# Open_Reactor_Control_System_-_System_Int.net
KiCad netlist of a schematic drawn in Altium Designer
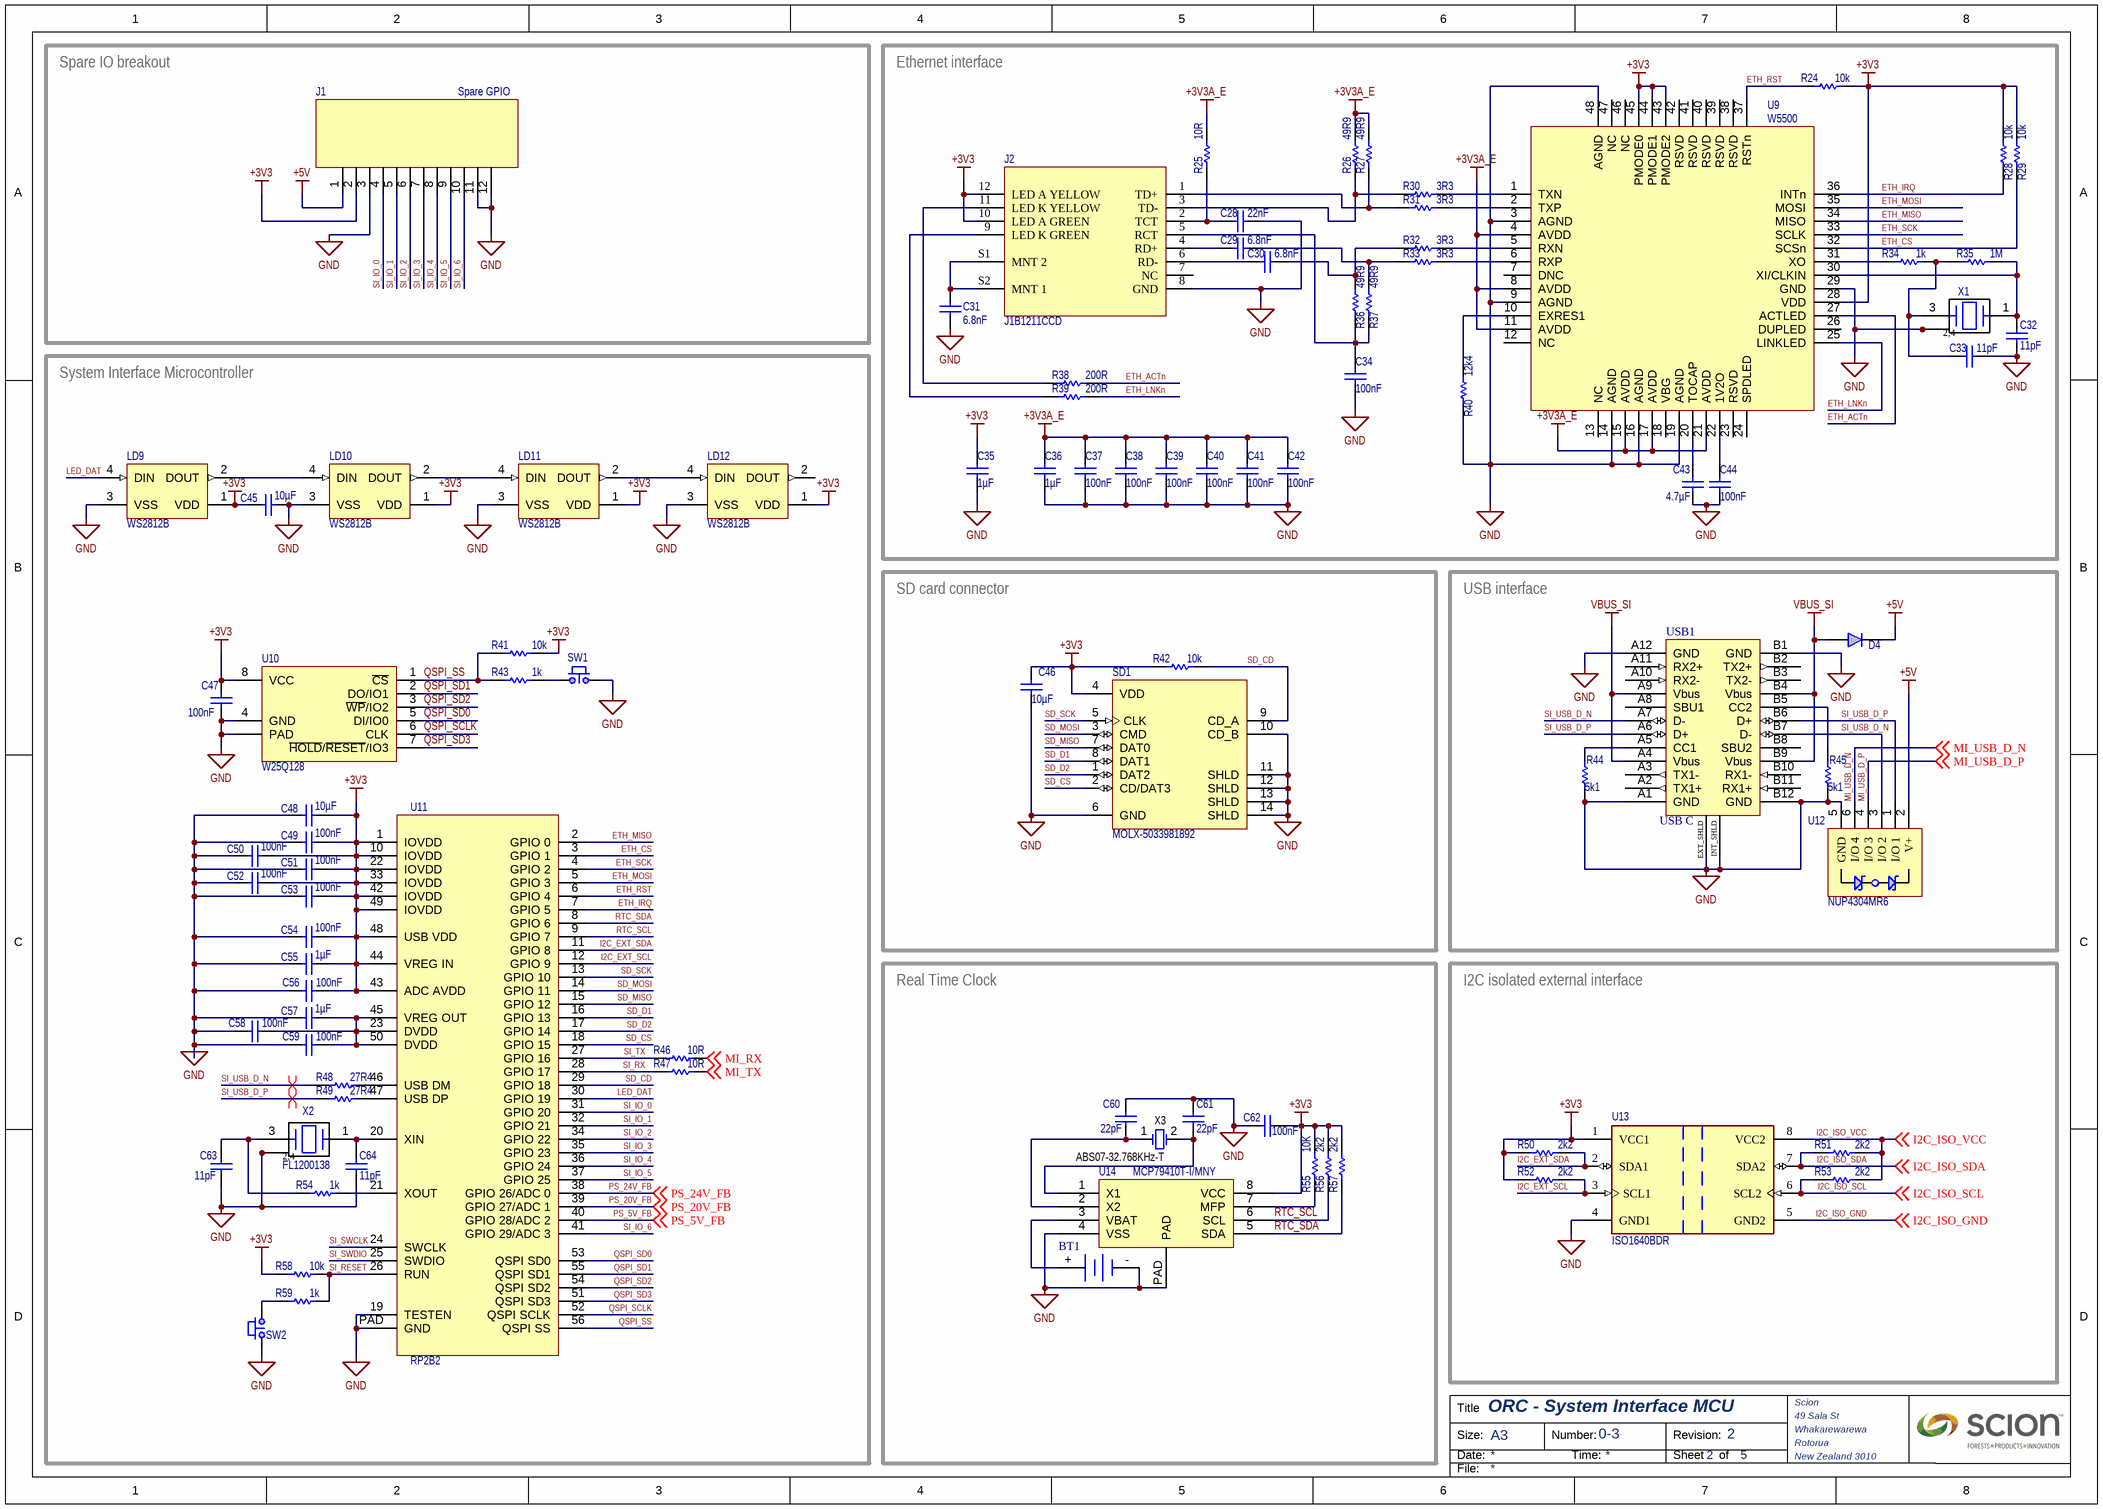
[diagram p0: Open Reactor Control System - System Interface MCU.SchDoc]

(export (version "E")
  (design (tool "Eeschema 10.0.6"))
  (components
    (comp (ref "BT1")
      (value "CR2032 Batt Holder")
      (footprint "CR2032 Batt Holder-Footprint-1")
      (description "SMD CR2032 coin cell holder")
      (libsource (lib "Scion Research") (part "CMP-00042-2"))
    )
    (comp (ref "C28")
      (value "22nF")
      (footprint "0603_CAP")
      (description "SMD Capacitor")
      (fields (field (name "Comment") "Capacitor"))
      (libsource (lib "Scion Research") (part "CMP-019-00005-2"))
    )
    (comp (ref "C29")
      (value "6.8nF")
      (footprint "0603_CAP")
      (description "SMD Capacitor")
      (fields (field (name "Comment") "Capacitor"))
      (libsource (lib "Scion Research") (part "CMP-019-00005-2"))
    )
    (comp (ref "C30")
      (value "6.8nF")
      (footprint "0603_CAP")
      (description "SMD Capacitor")
      (fields (field (name "Comment") "Capacitor"))
      (libsource (lib "Scion Research") (part "CMP-019-00005-2"))
    )
    (comp (ref "C31")
      (value "6.8nF")
      (footprint "0603_CAP")
      (description "SMD Capacitor")
      (fields (field (name "Comment") "Capacitor"))
      (libsource (lib "Scion Research") (part "CMP-019-00005-2"))
    )
    (comp (ref "C32")
      (value "11pF")
      (footprint "0603_CAP")
      (description "SMD Capacitor")
      (fields (field (name "Comment") "Capacitor"))
      (libsource (lib "Scion Research") (part "CMP-019-00005-2"))
    )
    (comp (ref "C33")
      (value "11pF")
      (footprint "0603_CAP")
      (description "SMD Capacitor")
      (fields (field (name "Comment") "Capacitor"))
      (libsource (lib "Scion Research") (part "CMP-019-00005-2"))
    )
    (comp (ref "C34")
      (value "100nF")
      (footprint "0603_CAP")
      (description "SMD Capacitor")
      (fields (field (name "Comment") "Capacitor"))
      (libsource (lib "Scion Research") (part "CMP-019-00005-2"))
    )
    (comp (ref "C35")
      (value "1µF")
      (footprint "0402_CAP")
      (description "SMD Capacitor")
      (fields (field (name "Comment") "Capacitor"))
      (libsource (lib "Scion Research") (part "CMP-019-00005-2"))
    )
    (comp (ref "C36")
      (value "1µF")
      (footprint "0402_CAP")
      (description "SMD Capacitor")
      (fields (field (name "Comment") "Capacitor"))
      (libsource (lib "Scion Research") (part "CMP-019-00005-2"))
    )
    (comp (ref "C37")
      (value "100nF")
      (footprint "0402_CAP")
      (description "SMD Capacitor")
      (fields (field (name "Comment") "Capacitor"))
      (libsource (lib "Scion Research") (part "CMP-019-00005-2"))
    )
    (comp (ref "C38")
      (value "100nF")
      (footprint "0402_CAP")
      (description "SMD Capacitor")
      (fields (field (name "Comment") "Capacitor"))
      (libsource (lib "Scion Research") (part "CMP-019-00005-2"))
    )
    (comp (ref "C39")
      (value "100nF")
      (footprint "0402_CAP")
      (description "SMD Capacitor")
      (fields (field (name "Comment") "Capacitor"))
      (libsource (lib "Scion Research") (part "CMP-019-00005-2"))
    )
    (comp (ref "C40")
      (value "100nF")
      (footprint "0402_CAP")
      (description "SMD Capacitor")
      (fields (field (name "Comment") "Capacitor"))
      (libsource (lib "Scion Research") (part "CMP-019-00005-2"))
    )
    (comp (ref "C41")
      (value "100nF")
      (footprint "0402_CAP")
      (description "SMD Capacitor")
      (fields (field (name "Comment") "Capacitor"))
      (libsource (lib "Scion Research") (part "CMP-019-00005-2"))
    )
    (comp (ref "C42")
      (value "100nF")
      (footprint "0402_CAP")
      (description "SMD Capacitor")
      (fields (field (name "Comment") "Capacitor"))
      (libsource (lib "Scion Research") (part "CMP-019-00005-2"))
    )
    (comp (ref "C43")
      (value "4.7µF")
      (footprint "0603_CAP")
      (description "SMD Capacitor")
      (fields (field (name "Comment") "Capacitor"))
      (libsource (lib "Scion Research") (part "CMP-019-00005-2"))
    )
    (comp (ref "C44")
      (value "100nF")
      (footprint "0402_CAP")
      (description "SMD Capacitor")
      (fields (field (name "Comment") "Capacitor"))
      (libsource (lib "Scion Research") (part "CMP-019-00005-2"))
    )
    (comp (ref "C45")
      (value "10µF")
      (footprint "0603_CAP")
      (description "SMD Capacitor")
      (fields (field (name "Comment") "Capacitor"))
      (libsource (lib "Scion Research") (part "CMP-019-00005-2"))
    )
    (comp (ref "C46")
      (value "10µF")
      (footprint "0603_CAP")
      (description "SMD Capacitor")
      (fields (field (name "Comment") "Capacitor"))
      (libsource (lib "Scion Research") (part "CMP-019-00005-2"))
    )
    (comp (ref "C47")
      (value "100nF")
      (footprint "0603_CAP")
      (description "SMD Capacitor")
      (fields (field (name "Comment") "Capacitor"))
      (libsource (lib "Scion Research") (part "CMP-019-00005-2"))
    )
    (comp (ref "C48")
      (value "10µF")
      (footprint "0603_CAP")
      (description "SMD Capacitor")
      (fields (field (name "Comment") "Capacitor"))
      (libsource (lib "Scion Research") (part "CMP-019-00005-2"))
    )
    (comp (ref "C49")
      (value "100nF")
      (footprint "0402_CAP")
      (description "SMD Capacitor")
      (fields (field (name "Comment") "Capacitor"))
      (libsource (lib "Scion Research") (part "CMP-019-00005-2"))
    )
    (comp (ref "C50")
      (value "100nF")
      (footprint "0402_CAP")
      (description "SMD Capacitor")
      (fields (field (name "Comment") "Capacitor"))
      (libsource (lib "Scion Research") (part "CMP-019-00005-2"))
    )
    (comp (ref "C51")
      (value "100nF")
      (footprint "0402_CAP")
      (description "SMD Capacitor")
      (fields (field (name "Comment") "Capacitor"))
      (libsource (lib "Scion Research") (part "CMP-019-00005-2"))
    )
    (comp (ref "C52")
      (value "100nF")
      (footprint "0402_CAP")
      (description "SMD Capacitor")
      (fields (field (name "Comment") "Capacitor"))
      (libsource (lib "Scion Research") (part "CMP-019-00005-2"))
    )
    (comp (ref "C53")
      (value "100nF")
      (footprint "0402_CAP")
      (description "SMD Capacitor")
      (fields (field (name "Comment") "Capacitor"))
      (libsource (lib "Scion Research") (part "CMP-019-00005-2"))
    )
    (comp (ref "C54")
      (value "100nF")
      (footprint "0402_CAP")
      (description "SMD Capacitor")
      (fields (field (name "Comment") "Capacitor"))
      (libsource (lib "Scion Research") (part "CMP-019-00005-2"))
    )
    (comp (ref "C55")
      (value "1µF")
      (footprint "0402_CAP")
      (description "SMD Capacitor")
      (fields (field (name "Comment") "Capacitor"))
      (libsource (lib "Scion Research") (part "CMP-019-00005-2"))
    )
    (comp (ref "C56")
      (value "100nF")
      (footprint "0402_CAP")
      (description "SMD Capacitor")
      (fields (field (name "Comment") "CMP-001-00172-2"))
      (libsource (lib "Scion Research") (part "CMP-019-00005-2"))
    )
    (comp (ref "C57")
      (value "1µF")
      (footprint "0402_CAP")
      (description "SMD Capacitor")
      (fields (field (name "Comment") "Capacitor"))
      (libsource (lib "Scion Research") (part "CMP-019-00005-2"))
    )
    (comp (ref "C58")
      (value "100nF")
      (footprint "0402_CAP")
      (description "SMD Capacitor")
      (fields (field (name "Comment") "CMP-001-00172-2"))
      (libsource (lib "Scion Research") (part "CMP-019-00005-2"))
    )
    (comp (ref "C59")
      (value "100nF")
      (footprint "0402_CAP")
      (description "SMD Capacitor")
      (fields (field (name "Comment") "CMP-001-00172-2"))
      (libsource (lib "Scion Research") (part "CMP-019-00005-2"))
    )
    (comp (ref "C60")
      (value "22pF")
      (footprint "0603_CAP")
      (description "SMD Capacitor")
      (fields (field (name "Comment") "Capacitor"))
      (libsource (lib "Scion Research") (part "CMP-019-00005-2"))
    )
    (comp (ref "C61")
      (value "22pF")
      (footprint "0603_CAP")
      (description "SMD Capacitor")
      (fields (field (name "Comment") "Capacitor"))
      (libsource (lib "Scion Research") (part "CMP-019-00005-2"))
    )
    (comp (ref "C62")
      (value "100nF")
      (footprint "0603_CAP")
      (description "SMD Capacitor")
      (fields (field (name "Comment") "Capacitor"))
      (libsource (lib "Scion Research") (part "CMP-019-00005-2"))
    )
    (comp (ref "C63")
      (value "11pF")
      (footprint "0603_CAP")
      (description "SMD Capacitor")
      (fields (field (name "Comment") "Capacitor"))
      (libsource (lib "Scion Research") (part "CMP-019-00005-2"))
    )
    (comp (ref "C64")
      (value "11pF")
      (footprint "0603_CAP")
      (description "SMD Capacitor")
      (fields (field (name "Comment") "Capacitor"))
      (libsource (lib "Scion Research") (part "CMP-019-00005-2"))
    )
    (comp (ref "D4")
      (value "Diode")
      (footprint "SOD-123")
      (description "SMD Diode")
      (libsource (lib "Scion Research") (part "Diode"))
    )
    (comp (ref "J1")
      (value "Spare GPIO")
      (footprint "12P DIP 2.54mm male header")
      (description "12 Pin Connector")
      (libsource (lib "Scion Research") (part "12_Pin"))
    )
    (comp (ref "J2")
      (value "J1B1211CCD")
      (footprint "FP-J1B1211CCD-MFG")
      (description "Telecom and Datacom Connector, 8 Contact(s), Female, Right Angle, Solder Terminal, Locking")
      (libsource (lib "Scion Research") (part "043a9053fb366fe6dc2bf5dbfb72c80"))
    )
    (comp (ref "LD9")
      (value "WS2812B")
      (footprint "WS2812B-2020")
      (fields (field (name "MANUFACTURER") "Adafruit Industries"))
      (libsource (lib "Scion Research") (part "CMP-007-00035-3"))
    )
    (comp (ref "LD10")
      (value "WS2812B")
      (footprint "WS2812B-2020")
      (fields (field (name "MANUFACTURER") "Adafruit Industries"))
      (libsource (lib "Scion Research") (part "CMP-007-00035-3"))
    )
    (comp (ref "LD11")
      (value "WS2812B")
      (footprint "WS2812B-2020")
      (fields (field (name "MANUFACTURER") "Adafruit Industries"))
      (libsource (lib "Scion Research") (part "CMP-007-00035-3"))
    )
    (comp (ref "LD12")
      (value "WS2812B")
      (footprint "WS2812B-2020")
      (fields (field (name "MANUFACTURER") "Adafruit Industries"))
      (libsource (lib "Scion Research") (part "CMP-007-00035-3"))
    )
    (comp (ref "R24")
      (value "Resistor")
      (footprint "0603_RES")
      (description "SMD Resistor")
      (fields (field (name "ALTIUM_VALUE") "10k"))
      (libsource (lib "Scion Research") (part "CMP-009-00177-2"))
    )
    (comp (ref "R25")
      (value "Resistor")
      (footprint "0603_RES")
      (description "SMD Resistor")
      (fields (field (name "ALTIUM_VALUE") "10R"))
      (libsource (lib "Scion Research") (part "CMP-009-00177-2"))
    )
    (comp (ref "R26")
      (value "Resistor")
      (footprint "0603_RES")
      (description "SMD Resistor")
      (fields (field (name "ALTIUM_VALUE") "49R9"))
      (libsource (lib "Scion Research") (part "CMP-009-00177-2"))
    )
    (comp (ref "R27")
      (value "Resistor")
      (footprint "0603_RES")
      (description "SMD Resistor")
      (fields (field (name "ALTIUM_VALUE") "49R9"))
      (libsource (lib "Scion Research") (part "CMP-009-00177-2"))
    )
    (comp (ref "R28")
      (value "10k")
      (footprint "0603_RES")
      (description "SMD Resistor")
      (fields (field (name "Comment") "Resistor"))
      (libsource (lib "Scion Research") (part "CMP-009-00177-2"))
    )
    (comp (ref "R29")
      (value "10k")
      (footprint "0603_RES")
      (description "SMD Resistor")
      (fields (field (name "Comment") "Resistor"))
      (libsource (lib "Scion Research") (part "CMP-009-00177-2"))
    )
    (comp (ref "R30")
      (value "Resistor")
      (footprint "0603_RES")
      (description "SMD Resistor")
      (fields (field (name "ALTIUM_VALUE") "3R3"))
      (libsource (lib "Scion Research") (part "CMP-009-00177-2"))
    )
    (comp (ref "R31")
      (value "Resistor")
      (footprint "0603_RES")
      (description "SMD Resistor")
      (fields (field (name "ALTIUM_VALUE") "3R3"))
      (libsource (lib "Scion Research") (part "CMP-009-00177-2"))
    )
    (comp (ref "R32")
      (value "Resistor")
      (footprint "0603_RES")
      (description "SMD Resistor")
      (fields (field (name "ALTIUM_VALUE") "3R3"))
      (libsource (lib "Scion Research") (part "CMP-009-00177-2"))
    )
    (comp (ref "R33")
      (value "Resistor")
      (footprint "0603_RES")
      (description "SMD Resistor")
      (fields (field (name "ALTIUM_VALUE") "3R3"))
      (libsource (lib "Scion Research") (part "CMP-009-00177-2"))
    )
    (comp (ref "R34")
      (value "Resistor")
      (footprint "0603_RES")
      (description "SMD Resistor")
      (fields (field (name "ALTIUM_VALUE") "1k"))
      (libsource (lib "Scion Research") (part "CMP-009-00177-2"))
    )
    (comp (ref "R35")
      (value "Resistor")
      (footprint "0603_RES")
      (description "SMD Resistor")
      (fields (field (name "ALTIUM_VALUE") "1M"))
      (libsource (lib "Scion Research") (part "CMP-009-00177-2"))
    )
    (comp (ref "R36")
      (value "Resistor")
      (footprint "0603_RES")
      (description "SMD Resistor")
      (fields (field (name "ALTIUM_VALUE") "49R9"))
      (libsource (lib "Scion Research") (part "CMP-009-00177-2"))
    )
    (comp (ref "R37")
      (value "Resistor")
      (footprint "0603_RES")
      (description "SMD Resistor")
      (fields (field (name "ALTIUM_VALUE") "49R9"))
      (libsource (lib "Scion Research") (part "CMP-009-00177-2"))
    )
    (comp (ref "R38")
      (value "Resistor")
      (footprint "0603_RES")
      (description "SMD Resistor")
      (fields (field (name "ALTIUM_VALUE") "200R"))
      (libsource (lib "Scion Research") (part "CMP-009-00177-2"))
    )
    (comp (ref "R39")
      (value "Resistor")
      (footprint "0603_RES")
      (description "SMD Resistor")
      (fields (field (name "ALTIUM_VALUE") "200R"))
      (libsource (lib "Scion Research") (part "CMP-009-00177-2"))
    )
    (comp (ref "R40")
      (value "12k4")
      (footprint "0603_RES")
      (description "SMD Resistor")
      (fields (field (name "Comment") "Resistor"))
      (libsource (lib "Scion Research") (part "CMP-009-00177-2"))
    )
    (comp (ref "R41")
      (value "10k")
      (footprint "0603_RES")
      (description "SMD Resistor")
      (fields (field (name "Comment") "Resistor"))
      (libsource (lib "Scion Research") (part "CMP-009-00177-2"))
    )
    (comp (ref "R42")
      (value "Resistor")
      (footprint "0603_RES")
      (description "SMD Resistor")
      (fields (field (name "ALTIUM_VALUE") "10k"))
      (libsource (lib "Scion Research") (part "CMP-009-00177-2"))
    )
    (comp (ref "R43")
      (value "1k")
      (footprint "0603_RES")
      (description "SMD Resistor")
      (fields (field (name "Comment") "Resistor"))
      (libsource (lib "Scion Research") (part "CMP-009-00177-2"))
    )
    (comp (ref "R44")
      (value "Resistor")
      (footprint "0603_RES")
      (description "SMD Resistor")
      (fields (field (name "ALTIUM_VALUE") "5k1"))
      (libsource (lib "Scion Research") (part "CMP-009-00177-2"))
    )
    (comp (ref "R45")
      (value "Resistor")
      (footprint "0603_RES")
      (description "SMD Resistor")
      (fields (field (name "ALTIUM_VALUE") "5k1"))
      (libsource (lib "Scion Research") (part "CMP-009-00177-2"))
    )
    (comp (ref "R46")
      (value "10R")
      (footprint "0603_RES")
      (description "SMD Resistor")
      (fields (field (name "Comment") "Resistor"))
      (libsource (lib "Scion Research") (part "CMP-009-00177-2"))
    )
    (comp (ref "R47")
      (value "10R")
      (footprint "0603_RES")
      (description "SMD Resistor")
      (fields (field (name "Comment") "Resistor"))
      (libsource (lib "Scion Research") (part "CMP-009-00177-2"))
    )
    (comp (ref "R48")
      (value "Resistor")
      (footprint "0603_RES")
      (description "SMD Resistor")
      (fields (field (name "ALTIUM_VALUE") "27R4"))
      (libsource (lib "Scion Research") (part "CMP-009-00177-2"))
    )
    (comp (ref "R49")
      (value "Resistor")
      (footprint "0603_RES")
      (description "SMD Resistor")
      (fields (field (name "ALTIUM_VALUE") "27R4"))
      (libsource (lib "Scion Research") (part "CMP-009-00177-2"))
    )
    (comp (ref "R50")
      (value "2k2")
      (footprint "0603_RES")
      (description "SMD Resistor")
      (fields (field (name "Comment") "Resistor"))
      (libsource (lib "Scion Research") (part "CMP-009-00177-2"))
    )
    (comp (ref "R51")
      (value "2k2")
      (footprint "0603_RES")
      (description "SMD Resistor")
      (fields (field (name "Comment") "Resistor"))
      (libsource (lib "Scion Research") (part "CMP-009-00177-2"))
    )
    (comp (ref "R52")
      (value "2k2")
      (footprint "0603_RES")
      (description "SMD Resistor")
      (fields (field (name "Comment") "Resistor"))
      (libsource (lib "Scion Research") (part "CMP-009-00177-2"))
    )
    (comp (ref "R53")
      (value "2k2")
      (footprint "0603_RES")
      (description "SMD Resistor")
      (fields (field (name "Comment") "Resistor"))
      (libsource (lib "Scion Research") (part "CMP-009-00177-2"))
    )
    (comp (ref "R54")
      (value "Resistor")
      (footprint "0603_RES")
      (description "SMD Resistor")
      (fields (field (name "ALTIUM_VALUE") "1k"))
      (libsource (lib "Scion Research") (part "CMP-009-00177-2"))
    )
    (comp (ref "R55")
      (value "10K")
      (footprint "0603_RES")
      (description "SMD Resistor")
      (fields (field (name "Comment") "Resistor"))
      (libsource (lib "Scion Research") (part "CMP-009-00177-2"))
    )
    (comp (ref "R56")
      (value "2k2")
      (footprint "0603_RES")
      (description "SMD Resistor")
      (fields (field (name "Comment") "Resistor"))
      (libsource (lib "Scion Research") (part "CMP-009-00177-2"))
    )
    (comp (ref "R57")
      (value "2k2")
      (footprint "0603_RES")
      (description "SMD Resistor")
      (fields (field (name "Comment") "Resistor"))
      (libsource (lib "Scion Research") (part "CMP-009-00177-2"))
    )
    (comp (ref "R58")
      (value "10k")
      (footprint "0603_RES")
      (description "SMD Resistor")
      (fields (field (name "Comment") "Resistor"))
      (libsource (lib "Scion Research") (part "CMP-009-00177-2"))
    )
    (comp (ref "R59")
      (value "1k")
      (footprint "0603_RES")
      (description "SMD Resistor")
      (fields (field (name "Comment") "Resistor"))
      (libsource (lib "Scion Research") (part "CMP-009-00177-2"))
    )
    (comp (ref "SD1")
      (value "MOLX-5033981892")
      (footprint "MOLX-5033981892_V")
      (libsource (lib "Scion Research") (part "CMP-002-00049-5"))
    )
    (comp (ref "SW1")
      (value "EVP-AAN02Q")
      (footprint "FP-EVP-AAN02Q-MFG")
      (description "Switch Tactile N.O. SPST Rectangular Button J-Bend 0.02A 15VDC 100000Cycles 5N SMD T/R")
      (libsource (lib "Scion Research") (part "67890d47754ac483cb1d3ba3be74b6c"))
    )
    (comp (ref "SW2")
      (value "EVP-AAN02Q")
      (footprint "FP-EVP-AAN02Q-MFG")
      (description "Switch Tactile N.O. SPST Rectangular Button J-Bend 0.02A 15VDC 100000Cycles 5N SMD T/R")
      (libsource (lib "Scion Research") (part "67890d47754ac483cb1d3ba3be74b6c"))
    )
    (comp (ref "U9")
      (value "W5500")
      (footprint "TSQFP50P900X900X160-48N")
      (description "Microprocessor Circuit, CMOS, PQFP48")
      (libsource (lib "Scion Research") (part "W5500-Symbol-1"))
    )
    (comp (ref "U10")
      (value "W25Q128")
      (footprint "SOIC127P790X216-8N")
      (description "W25Q16-256 SPI flash module")
      (libsource (lib "Scion Research") (part "W25Qxx-Symbol"))
    )
    (comp (ref "U11")
      (value "RP2B2")
      (footprint "QFN40P700X700X90_HS-57N")
      (description "RP2040 Arm Cortex M0+ Dual Core MCU")
      (libsource (lib "Scion Research") (part "RP2B2-Symbol-1"))
    )
    (comp (ref "U12")
      (value "NUP4304MR6")
      (footprint "TSOP-6")
      (description "ESD Protection Doide Array")
      (libsource (lib "Scion Research") (part "CMP-004-0028-1"))
    )
    (comp (ref "U13")
      (value "ISO1640BDR")
      (footprint "FP-D0008A-IPC_B")
      (description "Interface Circuit, PDSO8")
      (libsource (lib "Scion Research") (part "4cc1386e94c7f9b5035976a599e6ca5"))
    )
    (comp (ref "U14")
      (value "MCP79410T-I/MNY")
      (footprint "MCP79410T-I_MNY-Footprint-1")
      (description "Real Time Clock Serial 64byte Clock/Calendar/Alarm/Battery Backup Automotive 8-Pin TDFN EP T/R")
      (libsource (lib "Scion Research") (part "CMP-00046-1"))
    )
    (comp (ref "USB1")
      (value "USB C")
      (footprint "GT-USB-7010ASV")
      (description "Vertical or RA Type C Usb Connector Rohs Compliant: Yes")
      (libsource (lib "Scion Research") (part "CMP-00005-5"))
    )
    (comp (ref "X1")
      (value "ABM8-25.000MHZ-12-D1X-T")
      (footprint "3225 CRYSTAL 12MHz")
      (description "SMD Crystal")
      (libsource (lib "Scion Research") (part "Crystal 4-pin 3225"))
    )
    (comp (ref "X2")
      (value "FL1200138")
      (footprint "3225 CRYSTAL 12MHz")
      (description "SMD Crystal")
      (libsource (lib "Scion Research") (part "Crystal 4-pin 3225"))
    )
    (comp (ref "X3")
      (value "ABS07-32.768KHz-T")
      (footprint "ABRA-ABS07-2_V")
      (fields (field (name "TOLERANCE") "20ppm") (field (name "MANUFACTURER") "Abracon"))
      (libsource (lib "Scion Research") (part "CMP-003-00022-1"))
    )
  )
  (nets
    (net (code "1") (name "+3V3") (class "Default")
      (node (ref "C35") (pin "2") (pinfunction "2_2") (pintype "passive"))
      (node (ref "C45") (pin "2") (pinfunction "2_2") (pintype "passive"))
      (node (ref "C46") (pin "1") (pinfunction "1_1") (pintype "passive"))
      (node (ref "C47") (pin "1") (pinfunction "1_1") (pintype "passive"))
      (node (ref "C48") (pin "1") (pinfunction "1_1") (pintype "passive"))
      (node (ref "C49") (pin "1") (pinfunction "1_1") (pintype "passive"))
      (node (ref "C50") (pin "1") (pinfunction "1_1") (pintype "passive"))
      (node (ref "C51") (pin "1") (pinfunction "1_1") (pintype "passive"))
      (node (ref "C52") (pin "1") (pinfunction "1_1") (pintype "passive"))
      (node (ref "C53") (pin "1") (pinfunction "1_1") (pintype "passive"))
      (node (ref "C54") (pin "1") (pinfunction "1_1") (pintype "passive"))
      (node (ref "C55") (pin "1") (pinfunction "1_1") (pintype "passive"))
      (node (ref "C56") (pin "2") (pinfunction "2_2") (pintype "passive"))
      (node (ref "C62") (pin "1") (pinfunction "1_1") (pintype "passive"))
      (node (ref "J1") (pin "2") (pinfunction "2_2") (pintype "passive"))
      (node (ref "J2") (pin "10") (pinfunction "LED_A_GREEN_10") (pintype "passive"))
      (node (ref "J2") (pin "12") (pinfunction "LED_A_YELLOW_12") (pintype "passive"))
      (node (ref "LD10") (pin "1") (pinfunction "VDD_1") (pintype "power_in"))
      (node (ref "LD11") (pin "1") (pinfunction "VDD_1") (pintype "power_in"))
      (node (ref "LD12") (pin "1") (pinfunction "VDD_1") (pintype "power_in"))
      (node (ref "LD9") (pin "1") (pinfunction "VDD_1") (pintype "power_in"))
      (node (ref "R24") (pin "2") (pinfunction "2_2") (pintype "passive"))
      (node (ref "R28") (pin "2") (pinfunction "2_2") (pintype "passive"))
      (node (ref "R29") (pin "2") (pinfunction "2_2") (pintype "passive"))
      (node (ref "R41") (pin "2") (pinfunction "2_2") (pintype "passive"))
      (node (ref "R42") (pin "2") (pinfunction "2_2") (pintype "passive"))
      (node (ref "R50") (pin "2") (pinfunction "2_2") (pintype "passive"))
      (node (ref "R52") (pin "2") (pinfunction "2_2") (pintype "passive"))
      (node (ref "R55") (pin "2") (pinfunction "2_2") (pintype "passive"))
      (node (ref "R56") (pin "1") (pinfunction "1_1") (pintype "passive"))
      (node (ref "R57") (pin "1") (pinfunction "1_1") (pintype "passive"))
      (node (ref "R58") (pin "2") (pinfunction "2_2") (pintype "passive"))
      (node (ref "SD1") (pin "4") (pinfunction "VDD_4") (pintype "power_in"))
      (node (ref "U10") (pin "8") (pinfunction "VCC_8") (pintype "passive"))
      (node (ref "U11") (pin "1") (pinfunction "IOVDD_1") (pintype "passive"))
      (node (ref "U11") (pin "10") (pinfunction "IOVDD_10") (pintype "passive"))
      (node (ref "U11") (pin "22") (pinfunction "IOVDD_22") (pintype "passive"))
      (node (ref "U11") (pin "33") (pinfunction "IOVDD_33") (pintype "passive"))
      (node (ref "U11") (pin "42") (pinfunction "IOVDD_42") (pintype "passive"))
      (node (ref "U11") (pin "43") (pinfunction "ADC_AVDD_43") (pintype "passive"))
      (node (ref "U11") (pin "44") (pinfunction "VREG_IN_44") (pintype "passive"))
      (node (ref "U11") (pin "48") (pinfunction "USB_VDD_48") (pintype "passive"))
      (node (ref "U11") (pin "49") (pinfunction "IOVDD_49") (pintype "passive"))
      (node (ref "U13") (pin "1") (pinfunction "VCC1_1") (pintype "power_in"))
      (node (ref "U14") (pin "8") (pinfunction "VCC_8") (pintype "passive"))
      (node (ref "U9") (pin "28") (pinfunction "VDD_28") (pintype "passive"))
      (node (ref "U9") (pin "43") (pinfunction "PMODE2_43") (pintype "passive"))
      (node (ref "U9") (pin "44") (pinfunction "PMODE1_44") (pintype "passive"))
      (node (ref "U9") (pin "45") (pinfunction "PMODE0_45") (pintype "passive"))
    )
    (net (code "2") (name "+3V3A_E") (class "Default")
      (node (ref "C36") (pin "2") (pinfunction "2_2") (pintype "passive"))
      (node (ref "C37") (pin "2") (pinfunction "2_2") (pintype "passive"))
      (node (ref "C38") (pin "2") (pinfunction "2_2") (pintype "passive"))
      (node (ref "C39") (pin "2") (pinfunction "2_2") (pintype "passive"))
      (node (ref "C40") (pin "2") (pinfunction "2_2") (pintype "passive"))
      (node (ref "C41") (pin "2") (pinfunction "2_2") (pintype "passive"))
      (node (ref "C42") (pin "2") (pinfunction "2_2") (pintype "passive"))
      (node (ref "R25") (pin "2") (pinfunction "2_2") (pintype "passive"))
      (node (ref "R26") (pin "2") (pinfunction "2_2") (pintype "passive"))
      (node (ref "R27") (pin "2") (pinfunction "2_2") (pintype "passive"))
      (node (ref "U9") (pin "11") (pinfunction "AVDD_11") (pintype "passive"))
      (node (ref "U9") (pin "15") (pinfunction "AVDD_15") (pintype "passive"))
      (node (ref "U9") (pin "17") (pinfunction "AVDD_17") (pintype "passive"))
      (node (ref "U9") (pin "21") (pinfunction "AVDD_21") (pintype "passive"))
      (node (ref "U9") (pin "4") (pinfunction "AVDD_4") (pintype "passive"))
      (node (ref "U9") (pin "8") (pinfunction "AVDD_8") (pintype "passive"))
    )
    (net (code "3") (name "+5V") (class "Default")
      (node (ref "D4") (pin "1") (pinfunction "K_1") (pintype "passive"))
      (node (ref "J1") (pin "1") (pinfunction "1_1") (pintype "passive"))
      (node (ref "U12") (pin "2") (pinfunction "V+_2") (pintype "power_in"))
    )
    (net (code "4") (name "/ETH_ACTn") (class "Default")
      (node (ref "R38") (pin "2") (pinfunction "2_2") (pintype "passive"))
      (node (ref "U9") (pin "27") (pinfunction "ACTLED_27") (pintype "passive"))
    )
    (net (code "5") (name "/ETH_CS") (class "Default")
      (node (ref "R29") (pin "1") (pinfunction "1_1") (pintype "passive"))
      (node (ref "U11") (pin "3") (pinfunction "GPIO_1_3") (pintype "passive"))
      (node (ref "U9") (pin "32") (pinfunction "SCSn_32") (pintype "passive"))
    )
    (net (code "6") (name "/ETH_IRQ") (class "Default")
      (node (ref "R28") (pin "1") (pinfunction "1_1") (pintype "passive"))
      (node (ref "U11") (pin "7") (pinfunction "GPIO_5_7") (pintype "passive"))
      (node (ref "U9") (pin "36") (pinfunction "INTn_36") (pintype "passive"))
    )
    (net (code "7") (name "/ETH_LNKn") (class "Default")
      (node (ref "R39") (pin "2") (pinfunction "2_2") (pintype "passive"))
      (node (ref "U9") (pin "25") (pinfunction "LINKLED_25") (pintype "passive"))
    )
    (net (code "8") (name "/ETH_MISO") (class "Default")
      (node (ref "U11") (pin "2") (pinfunction "GPIO_0_2") (pintype "passive"))
      (node (ref "U9") (pin "34") (pinfunction "MISO_34") (pintype "passive"))
    )
    (net (code "9") (name "/ETH_MOSI") (class "Default")
      (node (ref "U11") (pin "5") (pinfunction "GPIO_3_5") (pintype "passive"))
      (node (ref "U9") (pin "35") (pinfunction "MOSI_35") (pintype "passive"))
    )
    (net (code "10") (name "/ETH_RST") (class "Default")
      (node (ref "R24") (pin "1") (pinfunction "1_1") (pintype "passive"))
      (node (ref "U11") (pin "6") (pinfunction "GPIO_4_6") (pintype "passive"))
      (node (ref "U9") (pin "37") (pinfunction "RSTn_37") (pintype "passive"))
    )
    (net (code "11") (name "/ETH_SCK") (class "Default")
      (node (ref "U11") (pin "4") (pinfunction "GPIO_2_4") (pintype "passive"))
      (node (ref "U9") (pin "33") (pinfunction "SCLK_33") (pintype "passive"))
    )
    (net (code "12") (name "/I2C_EXT_SCL") (class "Default")
      (node (ref "R52") (pin "1") (pinfunction "1_1") (pintype "passive"))
      (node (ref "U11") (pin "12") (pinfunction "GPIO_9_12") (pintype "passive"))
      (node (ref "U13") (pin "3") (pinfunction "SCL1_3") (pintype "input"))
    )
    (net (code "13") (name "/I2C_EXT_SDA") (class "Default")
      (node (ref "R50") (pin "1") (pinfunction "1_1") (pintype "passive"))
      (node (ref "U11") (pin "11") (pinfunction "GPIO_8_11") (pintype "passive"))
      (node (ref "U13") (pin "2") (pinfunction "SDA1_2") (pintype "bidirectional"))
    )
    (net (code "14") (name "/LED_DAT") (class "Default")
      (node (ref "LD9") (pin "4") (pinfunction "DIN_4") (pintype "input"))
      (node (ref "U11") (pin "30") (pinfunction "GPIO_19_30") (pintype "passive"))
    )
    (net (code "15") (name "/QSPI_SCLK") (class "Default")
      (node (ref "U10") (pin "6") (pinfunction "CLK_6") (pintype "passive"))
      (node (ref "U11") (pin "52") (pinfunction "QSPI_SCLK_52") (pintype "passive"))
    )
    (net (code "16") (name "/QSPI_SD0") (class "Default")
      (node (ref "U10") (pin "5") (pinfunction "DI/IO0_5") (pintype "passive"))
      (node (ref "U11") (pin "53") (pinfunction "QSPI_SD0_53") (pintype "passive"))
    )
    (net (code "17") (name "/QSPI_SD1") (class "Default")
      (node (ref "U10") (pin "2") (pinfunction "DO/IO1_2") (pintype "passive"))
      (node (ref "U11") (pin "55") (pinfunction "QSPI_SD1_55") (pintype "passive"))
    )
    (net (code "18") (name "/QSPI_SD2") (class "Default")
      (node (ref "U10") (pin "3") (pinfunction "~{WP}/IO2_3") (pintype "passive"))
      (node (ref "U11") (pin "54") (pinfunction "QSPI_SD2_54") (pintype "passive"))
    )
    (net (code "19") (name "/QSPI_SD3") (class "Default")
      (node (ref "U10") (pin "7") (pinfunction "~{HOLD}/~{RESET}/IO3_7") (pintype "passive"))
      (node (ref "U11") (pin "51") (pinfunction "QSPI_SD3_51") (pintype "passive"))
    )
    (net (code "20") (name "/QSPI_SS") (class "Default")
      (node (ref "R41") (pin "1") (pinfunction "1_1") (pintype "passive"))
      (node (ref "R43") (pin "2") (pinfunction "2_2") (pintype "passive"))
      (node (ref "U10") (pin "1") (pinfunction "~{CS}_1") (pintype "passive"))
      (node (ref "U11") (pin "56") (pinfunction "QSPI_SS_56") (pintype "passive"))
    )
    (net (code "21") (name "/RTC_SCL") (class "Default")
      (node (ref "R56") (pin "2") (pinfunction "2_2") (pintype "passive"))
      (node (ref "U11") (pin "9") (pinfunction "GPIO_7_9") (pintype "passive"))
      (node (ref "U14") (pin "6") (pinfunction "SCL_6") (pintype "passive"))
    )
    (net (code "22") (name "/RTC_SDA") (class "Default")
      (node (ref "R57") (pin "2") (pinfunction "2_2") (pintype "passive"))
      (node (ref "U11") (pin "8") (pinfunction "GPIO_6_8") (pintype "passive"))
      (node (ref "U14") (pin "5") (pinfunction "SDA_5") (pintype "passive"))
    )
    (net (code "23") (name "/SD_CD") (class "Default")
      (node (ref "R42") (pin "1") (pinfunction "1_1") (pintype "passive"))
      (node (ref "SD1") (pin "9") (pinfunction "CD_A_9") (pintype "passive"))
      (node (ref "U11") (pin "29") (pinfunction "GPIO_18_29") (pintype "passive"))
    )
    (net (code "24") (name "/SD_CS") (class "Default")
      (node (ref "SD1") (pin "2") (pinfunction "CD/DAT3_2") (pintype "bidirectional"))
      (node (ref "U11") (pin "18") (pinfunction "GPIO_15_18") (pintype "passive"))
    )
    (net (code "25") (name "/SD_D1") (class "Default")
      (node (ref "SD1") (pin "8") (pinfunction "DAT1_8") (pintype "bidirectional"))
      (node (ref "U11") (pin "16") (pinfunction "GPIO_13_16") (pintype "passive"))
    )
    (net (code "26") (name "/SD_D2") (class "Default")
      (node (ref "SD1") (pin "1") (pinfunction "DAT2_1") (pintype "bidirectional"))
      (node (ref "U11") (pin "17") (pinfunction "GPIO_14_17") (pintype "passive"))
    )
    (net (code "27") (name "/SD_MISO") (class "Default")
      (node (ref "SD1") (pin "7") (pinfunction "DAT0_7") (pintype "bidirectional"))
      (node (ref "U11") (pin "15") (pinfunction "GPIO_12_15") (pintype "passive"))
    )
    (net (code "28") (name "/SD_MOSI") (class "Default")
      (node (ref "SD1") (pin "3") (pinfunction "CMD_3") (pintype "bidirectional"))
      (node (ref "U11") (pin "14") (pinfunction "GPIO_11_14") (pintype "passive"))
    )
    (net (code "29") (name "/SD_SCK") (class "Default")
      (node (ref "SD1") (pin "5") (pinfunction "CLK_5") (pintype "input"))
      (node (ref "U11") (pin "13") (pinfunction "GPIO_10_13") (pintype "passive"))
    )
    (net (code "30") (name "/SI_IO_0") (class "Default")
      (node (ref "J1") (pin "4") (pinfunction "4_4") (pintype "passive"))
      (node (ref "U11") (pin "31") (pinfunction "GPIO_20_31") (pintype "passive"))
    )
    (net (code "31") (name "/SI_IO_1") (class "Default")
      (node (ref "J1") (pin "5") (pinfunction "5_5") (pintype "passive"))
      (node (ref "U11") (pin "32") (pinfunction "GPIO_21_32") (pintype "passive"))
    )
    (net (code "32") (name "/SI_IO_2") (class "Default")
      (node (ref "J1") (pin "6") (pinfunction "6_6") (pintype "passive"))
      (node (ref "U11") (pin "34") (pinfunction "GPIO_22_34") (pintype "passive"))
    )
    (net (code "33") (name "/SI_IO_3") (class "Default")
      (node (ref "J1") (pin "7") (pinfunction "7_7") (pintype "passive"))
      (node (ref "U11") (pin "35") (pinfunction "GPIO_23_35") (pintype "passive"))
    )
    (net (code "34") (name "/SI_IO_4") (class "Default")
      (node (ref "J1") (pin "8") (pinfunction "8_8") (pintype "passive"))
      (node (ref "U11") (pin "36") (pinfunction "GPIO_24_36") (pintype "passive"))
    )
    (net (code "35") (name "/SI_IO_5") (class "Default")
      (node (ref "J1") (pin "9") (pinfunction "9_9") (pintype "passive"))
      (node (ref "U11") (pin "37") (pinfunction "GPIO_25_37") (pintype "passive"))
    )
    (net (code "36") (name "/SI_IO_6") (class "Default")
      (node (ref "J1") (pin "10") (pinfunction "10_10") (pintype "passive"))
      (node (ref "U11") (pin "41") (pinfunction "GPIO_29/ADC_3_41") (pintype "passive"))
    )
    (net (code "37") (name "/SI_RESET") (class "Default")
      (node (ref "R58") (pin "1") (pinfunction "1_1") (pintype "passive"))
      (node (ref "R59") (pin "1") (pinfunction "1_1") (pintype "passive"))
      (node (ref "U11") (pin "26") (pinfunction "RUN_26") (pintype "passive"))
    )
    (net (code "38") (name "/SI_RX") (class "Default")
      (node (ref "R47") (pin "2") (pinfunction "2_2") (pintype "passive"))
      (node (ref "U11") (pin "28") (pinfunction "GPIO_17_28") (pintype "passive"))
    )
    (net (code "39") (name "/SI_SWCLK") (class "Default")
      (node (ref "U11") (pin "24") (pinfunction "SWCLK_24") (pintype "passive"))
    )
    (net (code "40") (name "/SI_SWDIO") (class "Default")
      (node (ref "U11") (pin "25") (pinfunction "SWDIO_25") (pintype "passive"))
    )
    (net (code "41") (name "/SI_TX") (class "Default")
      (node (ref "R46") (pin "2") (pinfunction "2_2") (pintype "passive"))
      (node (ref "U11") (pin "27") (pinfunction "GPIO_16_27") (pintype "passive"))
    )
    (net (code "42") (name "/SI_USB_D_N") (class "Default")
      (node (ref "R48") (pin "1") (pinfunction "1_1") (pintype "passive"))
      (node (ref "U12") (pin "3") (pinfunction "I/O_2_3") (pintype "power_in"))
      (node (ref "USB1") (pin "A7") (pinfunction "D-_A7") (pintype "bidirectional"))
      (node (ref "USB1") (pin "B7") (pinfunction "D-_B7") (pintype "bidirectional"))
    )
    (net (code "43") (name "/SI_USB_D_P") (class "Default")
      (node (ref "R49") (pin "1") (pinfunction "1_1") (pintype "passive"))
      (node (ref "U12") (pin "1") (pinfunction "I/O_1_1") (pintype "power_in"))
      (node (ref "USB1") (pin "A6") (pinfunction "D+_A6") (pintype "bidirectional"))
      (node (ref "USB1") (pin "B6") (pinfunction "D+_B6") (pintype "bidirectional"))
    )
    (net (code "44") (name "GND") (class "Default")
      (node (ref "BT1") (pin "-") (pinfunction "-_-") (pintype "passive"))
      (node (ref "C28") (pin "1") (pinfunction "1_1") (pintype "passive"))
      (node (ref "C31") (pin "2") (pinfunction "2_2") (pintype "passive"))
      (node (ref "C32") (pin "2") (pinfunction "2_2") (pintype "passive"))
      (node (ref "C33") (pin "2") (pinfunction "2_2") (pintype "passive"))
      (node (ref "C34") (pin "1") (pinfunction "1_1") (pintype "passive"))
      (node (ref "C35") (pin "1") (pinfunction "1_1") (pintype "passive"))
      (node (ref "C36") (pin "1") (pinfunction "1_1") (pintype "passive"))
      (node (ref "C37") (pin "1") (pinfunction "1_1") (pintype "passive"))
      (node (ref "C38") (pin "1") (pinfunction "1_1") (pintype "passive"))
      (node (ref "C39") (pin "1") (pinfunction "1_1") (pintype "passive"))
      (node (ref "C40") (pin "1") (pinfunction "1_1") (pintype "passive"))
      (node (ref "C41") (pin "1") (pinfunction "1_1") (pintype "passive"))
      (node (ref "C42") (pin "1") (pinfunction "1_1") (pintype "passive"))
      (node (ref "C43") (pin "1") (pinfunction "1_1") (pintype "passive"))
      (node (ref "C44") (pin "1") (pinfunction "1_1") (pintype "passive"))
      (node (ref "C45") (pin "1") (pinfunction "1_1") (pintype "passive"))
      (node (ref "C46") (pin "2") (pinfunction "2_2") (pintype "passive"))
      (node (ref "C47") (pin "2") (pinfunction "2_2") (pintype "passive"))
      (node (ref "C48") (pin "2") (pinfunction "2_2") (pintype "passive"))
      (node (ref "C49") (pin "2") (pinfunction "2_2") (pintype "passive"))
      (node (ref "C50") (pin "2") (pinfunction "2_2") (pintype "passive"))
      (node (ref "C51") (pin "2") (pinfunction "2_2") (pintype "passive"))
      (node (ref "C52") (pin "2") (pinfunction "2_2") (pintype "passive"))
      (node (ref "C53") (pin "2") (pinfunction "2_2") (pintype "passive"))
      (node (ref "C54") (pin "2") (pinfunction "2_2") (pintype "passive"))
      (node (ref "C55") (pin "2") (pinfunction "2_2") (pintype "passive"))
      (node (ref "C56") (pin "1") (pinfunction "1_1") (pintype "passive"))
      (node (ref "C57") (pin "2") (pinfunction "2_2") (pintype "passive"))
      (node (ref "C58") (pin "1") (pinfunction "1_1") (pintype "passive"))
      (node (ref "C59") (pin "1") (pinfunction "1_1") (pintype "passive"))
      (node (ref "C60") (pin "2") (pinfunction "2_2") (pintype "passive"))
      (node (ref "C61") (pin "2") (pinfunction "2_2") (pintype "passive"))
      (node (ref "C62") (pin "2") (pinfunction "2_2") (pintype "passive"))
      (node (ref "C63") (pin "2") (pinfunction "2_2") (pintype "passive"))
      (node (ref "C64") (pin "2") (pinfunction "2_2") (pintype "passive"))
      (node (ref "J1") (pin "11") (pinfunction "11_11") (pintype "passive"))
      (node (ref "J1") (pin "12") (pinfunction "12_12") (pintype "passive"))
      (node (ref "J1") (pin "3") (pinfunction "3_3") (pintype "passive"))
      (node (ref "J2") (pin "8") (pinfunction "GND_8") (pintype "passive"))
      (node (ref "LD10") (pin "3") (pinfunction "VSS_3") (pintype "power_in"))
      (node (ref "LD11") (pin "3") (pinfunction "VSS_3") (pintype "power_in"))
      (node (ref "LD12") (pin "3") (pinfunction "VSS_3") (pintype "power_in"))
      (node (ref "LD9") (pin "3") (pinfunction "VSS_3") (pintype "power_in"))
      (node (ref "R40") (pin "1") (pinfunction "1_1") (pintype "passive"))
      (node (ref "R44") (pin "2") (pinfunction "2_2") (pintype "passive"))
      (node (ref "R45") (pin "2") (pinfunction "2_2") (pintype "passive"))
      (node (ref "SD1") (pin "10") (pinfunction "CD_B_10") (pintype "passive"))
      (node (ref "SD1") (pin "11") (pinfunction "SHLD_11") (pintype "passive"))
      (node (ref "SD1") (pin "12") (pinfunction "SHLD_12") (pintype "passive"))
      (node (ref "SD1") (pin "13") (pinfunction "SHLD_13") (pintype "passive"))
      (node (ref "SD1") (pin "14") (pinfunction "SHLD_14") (pintype "passive"))
      (node (ref "SD1") (pin "6") (pinfunction "GND_6") (pintype "passive"))
      (node (ref "SW1") (pin "2") (pinfunction "2_2") (pintype "passive"))
      (node (ref "SW2") (pin "1") (pinfunction "1_1") (pintype "passive"))
      (node (ref "U10") (pin "4") (pinfunction "GND_4") (pintype "passive"))
      (node (ref "U10") (pin "PAD") (pinfunction "PAD_PAD") (pintype "passive"))
      (node (ref "U11") (pin "19") (pinfunction "TESTEN_19") (pintype "passive"))
      (node (ref "U11") (pin "PAD") (pinfunction "GND_PAD") (pintype "passive"))
      (node (ref "U12") (pin "5") (pinfunction "GND_5") (pintype "power_in"))
      (node (ref "U13") (pin "4") (pinfunction "GND1_4") (pintype "power_in"))
      (node (ref "U14") (pin "4") (pinfunction "VSS_4") (pintype "passive"))
      (node (ref "U14") (pin "PAD") (pinfunction "PAD_PAD") (pintype "passive"))
      (node (ref "U9") (pin "14") (pinfunction "AGND_14") (pintype "passive"))
      (node (ref "U9") (pin "16") (pinfunction "AGND_16") (pintype "passive"))
      (node (ref "U9") (pin "19") (pinfunction "AGND_19") (pintype "passive"))
      (node (ref "U9") (pin "29") (pinfunction "GND_29") (pintype "passive"))
      (node (ref "U9") (pin "3") (pinfunction "AGND_3") (pintype "passive"))
      (node (ref "U9") (pin "48") (pinfunction "AGND_48") (pintype "passive"))
      (node (ref "U9") (pin "9") (pinfunction "AGND_9") (pintype "passive"))
      (node (ref "USB1") (pin "A1") (pinfunction "GND_A1") (pintype "power_in"))
      (node (ref "USB1") (pin "A12") (pinfunction "GND_A12") (pintype "power_in"))
      (node (ref "USB1") (pin "B1") (pinfunction "GND_B1") (pintype "power_in"))
      (node (ref "USB1") (pin "B12") (pinfunction "GND_B12") (pintype "power_in"))
      (node (ref "USB1") (pin "EXT_SHLD") (pintype "passive"))
      (node (ref "USB1") (pin "INT_SHLD") (pintype "passive"))
      (node (ref "X1") (pin "2") (pinfunction "GND_2") (pintype "passive"))
      (node (ref "X1") (pin "4") (pinfunction "GND_4") (pintype "passive"))
      (node (ref "X2") (pin "2") (pinfunction "GND_2") (pintype "passive"))
      (node (ref "X2") (pin "4") (pinfunction "GND_4") (pintype "passive"))
    )
    (net (code "45") (name "I2C_ISO_GND") (class "Default")
      (node (ref "U13") (pin "5") (pinfunction "GND2_5") (pintype "power_in"))
    )
    (net (code "46") (name "I2C_ISO_SCL") (class "Default")
      (node (ref "R53") (pin "2") (pinfunction "2_2") (pintype "passive"))
      (node (ref "U13") (pin "6") (pinfunction "SCL2_6") (pintype "input"))
    )
    (net (code "47") (name "I2C_ISO_SDA") (class "Default")
      (node (ref "R51") (pin "2") (pinfunction "2_2") (pintype "passive"))
      (node (ref "U13") (pin "7") (pinfunction "SDA2_7") (pintype "bidirectional"))
    )
    (net (code "48") (name "I2C_ISO_VCC") (class "Default")
      (node (ref "R51") (pin "1") (pinfunction "1_1") (pintype "passive"))
      (node (ref "R53") (pin "1") (pinfunction "1_1") (pintype "passive"))
      (node (ref "U13") (pin "8") (pinfunction "VCC2_8") (pintype "power_in"))
    )
    (net (code "49") (name "MI_RX") (class "Default")
      (node (ref "R46") (pin "1") (pinfunction "1_1") (pintype "passive"))
    )
    (net (code "50") (name "MI_TX") (class "Default")
      (node (ref "R47") (pin "1") (pinfunction "1_1") (pintype "passive"))
    )
    (net (code "51") (name "MI_USB_D_N") (class "Default")
      (node (ref "U12") (pin "6") (pinfunction "I/O_4_6") (pintype "power_in"))
    )
    (net (code "52") (name "MI_USB_D_P") (class "Default")
      (node (ref "U12") (pin "4") (pinfunction "I/O_3_4") (pintype "power_in"))
    )
    (net (code "53") (name "Net-(C29-Pad1)") (class "Default")
      (node (ref "C29") (pin "1") (pinfunction "1_1") (pintype "passive"))
      (node (ref "R33") (pin "1") (pinfunction "1_1") (pintype "passive"))
      (node (ref "R37") (pin "2") (pinfunction "2_2") (pintype "passive"))
    )
    (net (code "54") (name "Net-(C30-Pad1)") (class "Default")
      (node (ref "C30") (pin "1") (pinfunction "1_1") (pintype "passive"))
      (node (ref "R32") (pin "1") (pinfunction "1_1") (pintype "passive"))
      (node (ref "R36") (pin "2") (pinfunction "2_2") (pintype "passive"))
    )
    (net (code "55") (name "Net-(C33-Pad1)") (class "Default")
      (node (ref "C33") (pin "1") (pinfunction "1_1") (pintype "passive"))
      (node (ref "R34") (pin "2") (pinfunction "2_2") (pintype "passive"))
      (node (ref "R35") (pin "1") (pinfunction "1_1") (pintype "passive"))
      (node (ref "X1") (pin "3") (pinfunction "XT_3") (pintype "passive"))
    )
    (net (code "56") (name "Net-(C63-Pad1)") (class "Default")
      (node (ref "C63") (pin "1") (pinfunction "1_1") (pintype "passive"))
      (node (ref "R54") (pin "1") (pinfunction "1_1") (pintype "passive"))
      (node (ref "X2") (pin "3") (pinfunction "XT_3") (pintype "passive"))
    )
    (net (code "57") (name "Net-(J2-LED_K_GREEN)") (class "Default")
      (node (ref "J2") (pin "9") (pinfunction "LED_K_GREEN_9") (pintype "passive"))
      (node (ref "R39") (pin "1") (pinfunction "1_1") (pintype "passive"))
    )
    (net (code "58") (name "Net-(J2-LED_K_YELLOW)") (class "Default")
      (node (ref "J2") (pin "11") (pinfunction "LED_K_YELLOW_11") (pintype "passive"))
      (node (ref "R38") (pin "1") (pinfunction "1_1") (pintype "passive"))
    )
    (net (code "59") (name "Net-(J2-MNT_1)") (class "Default")
      (node (ref "C31") (pin "1") (pinfunction "1_1") (pintype "passive"))
      (node (ref "J2") (pin "S1") (pinfunction "MNT_2_S1") (pintype "passive"))
      (node (ref "J2") (pin "S2") (pinfunction "MNT_1_S2") (pintype "passive"))
    )
    (net (code "60") (name "Net-(J2-RCT)") (class "Default")
      (node (ref "C34") (pin "2") (pinfunction "2_2") (pintype "passive"))
      (node (ref "J2") (pin "5") (pinfunction "RCT_5") (pintype "passive"))
      (node (ref "R36") (pin "1") (pinfunction "1_1") (pintype "passive"))
      (node (ref "R37") (pin "1") (pinfunction "1_1") (pintype "passive"))
    )
    (net (code "61") (name "Net-(J2-RD+)") (class "Default")
      (node (ref "C29") (pin "2") (pinfunction "2_2") (pintype "passive"))
      (node (ref "J2") (pin "4") (pinfunction "RD+_4") (pintype "passive"))
    )
    (net (code "62") (name "Net-(J2-RD-)") (class "Default")
      (node (ref "C30") (pin "2") (pinfunction "2_2") (pintype "passive"))
      (node (ref "J2") (pin "6") (pinfunction "RD-_6") (pintype "passive"))
    )
    (net (code "63") (name "Net-(J2-TCT)") (class "Default")
      (node (ref "C28") (pin "2") (pinfunction "2_2") (pintype "passive"))
      (node (ref "J2") (pin "2") (pinfunction "TCT_2") (pintype "passive"))
      (node (ref "R25") (pin "1") (pinfunction "1_1") (pintype "passive"))
    )
    (net (code "64") (name "Net-(J2-TD+)") (class "Default")
      (node (ref "J2") (pin "1") (pinfunction "TD+_1") (pintype "passive"))
      (node (ref "R27") (pin "1") (pinfunction "1_1") (pintype "passive"))
      (node (ref "R31") (pin "1") (pinfunction "1_1") (pintype "passive"))
    )
    (net (code "65") (name "Net-(J2-TD-)") (class "Default")
      (node (ref "J2") (pin "3") (pinfunction "TD-_3") (pintype "passive"))
      (node (ref "R26") (pin "1") (pinfunction "1_1") (pintype "passive"))
      (node (ref "R30") (pin "1") (pinfunction "1_1") (pintype "passive"))
    )
    (net (code "66") (name "Net-(LD10-DIN)") (class "Default")
      (node (ref "LD10") (pin "4") (pinfunction "DIN_4") (pintype "input"))
      (node (ref "LD9") (pin "2") (pinfunction "DOUT_2") (pintype "output"))
    )
    (net (code "67") (name "Net-(LD10-DOUT)") (class "Default")
      (node (ref "LD10") (pin "2") (pinfunction "DOUT_2") (pintype "output"))
      (node (ref "LD11") (pin "4") (pinfunction "DIN_4") (pintype "input"))
    )
    (net (code "68") (name "Net-(LD11-DOUT)") (class "Default")
      (node (ref "LD11") (pin "2") (pinfunction "DOUT_2") (pintype "output"))
      (node (ref "LD12") (pin "4") (pinfunction "DIN_4") (pintype "input"))
    )
    (net (code "69") (name "Net-(R43-Pad1)") (class "Default")
      (node (ref "R43") (pin "1") (pinfunction "1_1") (pintype "passive"))
      (node (ref "SW1") (pin "1") (pinfunction "1_1") (pintype "passive"))
    )
    (net (code "70") (name "Net-(R59-Pad2)") (class "Default")
      (node (ref "R59") (pin "2") (pinfunction "2_2") (pintype "passive"))
      (node (ref "SW2") (pin "2") (pinfunction "2_2") (pintype "passive"))
    )
    (net (code "71") (name "Net-(U9-1V2O)") (class "Default")
      (node (ref "C44") (pin "2") (pinfunction "2_2") (pintype "passive"))
      (node (ref "U9") (pin "22") (pinfunction "1V2O_22") (pintype "passive"))
    )
    (net (code "72") (name "Net-(U9-EXRES1)") (class "Default")
      (node (ref "R40") (pin "2") (pinfunction "2_2") (pintype "passive"))
      (node (ref "U9") (pin "10") (pinfunction "EXRES1_10") (pintype "passive"))
    )
    (net (code "73") (name "Net-(U9-RXN)") (class "Default")
      (node (ref "R32") (pin "2") (pinfunction "2_2") (pintype "passive"))
      (node (ref "U9") (pin "5") (pinfunction "RXN_5") (pintype "passive"))
    )
    (net (code "74") (name "Net-(U9-RXP)") (class "Default")
      (node (ref "R33") (pin "2") (pinfunction "2_2") (pintype "passive"))
      (node (ref "U9") (pin "6") (pinfunction "RXP_6") (pintype "passive"))
    )
    (net (code "75") (name "Net-(U9-TOCAP)") (class "Default")
      (node (ref "C43") (pin "2") (pinfunction "2_2") (pintype "passive"))
      (node (ref "U9") (pin "20") (pinfunction "TOCAP_20") (pintype "passive"))
    )
    (net (code "76") (name "Net-(U9-TXN)") (class "Default")
      (node (ref "R30") (pin "2") (pinfunction "2_2") (pintype "passive"))
      (node (ref "U9") (pin "1") (pinfunction "TXN_1") (pintype "passive"))
    )
    (net (code "77") (name "Net-(U9-TXP)") (class "Default")
      (node (ref "R31") (pin "2") (pinfunction "2_2") (pintype "passive"))
      (node (ref "U9") (pin "2") (pinfunction "TXP_2") (pintype "passive"))
    )
    (net (code "78") (name "Net-(U9-XI{slash}CLKIN)") (class "Default")
      (node (ref "C32") (pin "1") (pinfunction "1_1") (pintype "passive"))
      (node (ref "R35") (pin "2") (pinfunction "2_2") (pintype "passive"))
      (node (ref "U9") (pin "30") (pinfunction "XI/CLKIN_30") (pintype "passive"))
      (node (ref "X1") (pin "1") (pinfunction "XT_1") (pintype "passive"))
    )
    (net (code "79") (name "Net-(U9-XO)") (class "Default")
      (node (ref "R34") (pin "1") (pinfunction "1_1") (pintype "passive"))
      (node (ref "U9") (pin "31") (pinfunction "XO_31") (pintype "passive"))
    )
    (net (code "80") (name "Net-(U11-USB_DM)") (class "Default")
      (node (ref "R48") (pin "2") (pinfunction "2_2") (pintype "passive"))
      (node (ref "U11") (pin "46") (pinfunction "USB_DM_46") (pintype "passive"))
    )
    (net (code "81") (name "Net-(U11-USB_DP)") (class "Default")
      (node (ref "R49") (pin "2") (pinfunction "2_2") (pintype "passive"))
      (node (ref "U11") (pin "47") (pinfunction "USB_DP_47") (pintype "passive"))
    )
    (net (code "82") (name "Net-(U11-VREG_OUT)") (class "Default")
      (node (ref "C57") (pin "1") (pinfunction "1_1") (pintype "passive"))
      (node (ref "C58") (pin "2") (pinfunction "2_2") (pintype "passive"))
      (node (ref "C59") (pin "2") (pinfunction "2_2") (pintype "passive"))
      (node (ref "U11") (pin "23") (pinfunction "DVDD_23") (pintype "passive"))
      (node (ref "U11") (pin "45") (pinfunction "VREG_OUT_45") (pintype "passive"))
      (node (ref "U11") (pin "50") (pinfunction "DVDD_50") (pintype "passive"))
    )
    (net (code "83") (name "Net-(U11-XIN)") (class "Default")
      (node (ref "C64") (pin "1") (pinfunction "1_1") (pintype "passive"))
      (node (ref "U11") (pin "20") (pinfunction "XIN_20") (pintype "passive"))
      (node (ref "X2") (pin "1") (pinfunction "XT_1") (pintype "passive"))
    )
    (net (code "84") (name "Net-(U11-XOUT)") (class "Default")
      (node (ref "R54") (pin "2") (pinfunction "2_2") (pintype "passive"))
      (node (ref "U11") (pin "21") (pinfunction "XOUT_21") (pintype "passive"))
    )
    (net (code "85") (name "Net-(U14-MFP)") (class "Default")
      (node (ref "R55") (pin "1") (pinfunction "1_1") (pintype "passive"))
      (node (ref "U14") (pin "7") (pinfunction "MFP_7") (pintype "passive"))
    )
    (net (code "86") (name "Net-(U14-VBAT)") (class "Default")
      (node (ref "BT1") (pin "+") (pinfunction "+_+") (pintype "passive"))
      (node (ref "U14") (pin "3") (pinfunction "VBAT_3") (pintype "passive"))
    )
    (net (code "87") (name "Net-(U14-X1)") (class "Default")
      (node (ref "C61") (pin "1") (pinfunction "1_1") (pintype "passive"))
      (node (ref "U14") (pin "1") (pinfunction "X1_1") (pintype "passive"))
      (node (ref "X3") (pin "2") (pinfunction "OSC2_2") (pintype "passive"))
    )
    (net (code "88") (name "Net-(U14-X2)") (class "Default")
      (node (ref "C60") (pin "1") (pinfunction "1_1") (pintype "passive"))
      (node (ref "U14") (pin "2") (pinfunction "X2_2") (pintype "passive"))
      (node (ref "X3") (pin "1") (pinfunction "OSC1_1") (pintype "passive"))
    )
    (net (code "89") (name "Net-(USB1-CC1)") (class "Default")
      (node (ref "R44") (pin "1") (pinfunction "1_1") (pintype "passive"))
      (node (ref "USB1") (pin "A5") (pinfunction "CC1_A5") (pintype "passive"))
    )
    (net (code "90") (name "Net-(USB1-CC2)") (class "Default")
      (node (ref "R45") (pin "1") (pinfunction "1_1") (pintype "passive"))
      (node (ref "USB1") (pin "B5") (pinfunction "CC2_B5") (pintype "passive"))
    )
    (net (code "91") (name "PS_5V_FB") (class "Default")
      (node (ref "U11") (pin "40") (pinfunction "GPIO_28/ADC_2_40") (pintype "passive"))
    )
    (net (code "92") (name "PS_20V_FB") (class "Default")
      (node (ref "U11") (pin "39") (pinfunction "GPIO_27/ADC_1_39") (pintype "passive"))
    )
    (net (code "93") (name "PS_24V_FB") (class "Default")
      (node (ref "U11") (pin "38") (pinfunction "GPIO_26/ADC_0_38") (pintype "passive"))
    )
    (net (code "94") (name "VBUS_SI") (class "Default")
      (node (ref "D4") (pin "2") (pinfunction "A_2") (pintype "passive"))
      (node (ref "USB1") (pin "A4") (pinfunction "Vbus_A4") (pintype "power_in"))
      (node (ref "USB1") (pin "A9") (pinfunction "Vbus_A9") (pintype "power_in"))
      (node (ref "USB1") (pin "B4") (pinfunction "Vbus_B4") (pintype "power_in"))
      (node (ref "USB1") (pin "B9") (pinfunction "Vbus_B9") (pintype "power_in"))
    )
    (net (code "95") (name "unconnected-(J2-NC-Pad7)") (class "Default")
      (node (ref "J2") (pin "7") (pinfunction "NC_7") (pintype "passive"))
    )
    (net (code "96") (name "unconnected-(LD12-DOUT-Pad2)") (class "Default")
      (node (ref "LD12") (pin "2") (pinfunction "DOUT_2") (pintype "output"))
    )
    (net (code "97") (name "unconnected-(U9-DNC-Pad7)") (class "Default")
      (node (ref "U9") (pin "7") (pinfunction "DNC_7") (pintype "passive"))
    )
    (net (code "98") (name "unconnected-(U9-DUPLED-Pad26)") (class "Default")
      (node (ref "U9") (pin "26") (pinfunction "DUPLED_26") (pintype "passive"))
    )
    (net (code "99") (name "unconnected-(U9-NC-Pad12)") (class "Default")
      (node (ref "U9") (pin "12") (pinfunction "NC_12") (pintype "passive"))
    )
    (net (code "100") (name "unconnected-(U9-NC-Pad13)") (class "Default")
      (node (ref "U9") (pin "13") (pinfunction "NC_13") (pintype "passive"))
    )
    (net (code "101") (name "unconnected-(U9-NC-Pad46)") (class "Default")
      (node (ref "U9") (pin "46") (pinfunction "NC_46") (pintype "passive"))
    )
    (net (code "102") (name "unconnected-(U9-NC-Pad47)") (class "Default")
      (node (ref "U9") (pin "47") (pinfunction "NC_47") (pintype "passive"))
    )
    (net (code "103") (name "unconnected-(U9-RSVD-Pad23)") (class "Default")
      (node (ref "U9") (pin "23") (pinfunction "RSVD_23") (pintype "passive"))
    )
    (net (code "104") (name "unconnected-(U9-RSVD-Pad38)") (class "Default")
      (node (ref "U9") (pin "38") (pinfunction "RSVD_38") (pintype "passive"))
    )
    (net (code "105") (name "unconnected-(U9-RSVD-Pad39)") (class "Default")
      (node (ref "U9") (pin "39") (pinfunction "RSVD_39") (pintype "passive"))
    )
    (net (code "106") (name "unconnected-(U9-RSVD-Pad40)") (class "Default")
      (node (ref "U9") (pin "40") (pinfunction "RSVD_40") (pintype "passive"))
    )
    (net (code "107") (name "unconnected-(U9-RSVD-Pad41)") (class "Default")
      (node (ref "U9") (pin "41") (pinfunction "RSVD_41") (pintype "passive"))
    )
    (net (code "108") (name "unconnected-(U9-RSVD-Pad42)") (class "Default")
      (node (ref "U9") (pin "42") (pinfunction "RSVD_42") (pintype "passive"))
    )
    (net (code "109") (name "unconnected-(U9-SPDLED-Pad24)") (class "Default")
      (node (ref "U9") (pin "24") (pinfunction "SPDLED_24") (pintype "passive"))
    )
    (net (code "110") (name "unconnected-(U9-VBG-Pad18)") (class "Default")
      (node (ref "U9") (pin "18") (pinfunction "VBG_18") (pintype "passive"))
    )
    (net (code "111") (name "unconnected-(USB1-RX1+-PadB11)") (class "Default")
      (node (ref "USB1") (pin "B11") (pinfunction "RX1+_B11") (pintype "input"))
    )
    (net (code "112") (name "unconnected-(USB1-RX1--PadB10)") (class "Default")
      (node (ref "USB1") (pin "B10") (pinfunction "RX1-_B10") (pintype "input"))
    )
    (net (code "113") (name "unconnected-(USB1-RX2+-PadA11)") (class "Default")
      (node (ref "USB1") (pin "A11") (pinfunction "RX2+_A11") (pintype "input"))
    )
    (net (code "114") (name "unconnected-(USB1-RX2--PadA10)") (class "Default")
      (node (ref "USB1") (pin "A10") (pinfunction "RX2-_A10") (pintype "input"))
    )
    (net (code "115") (name "unconnected-(USB1-SBU1-PadA8)") (class "Default")
      (node (ref "USB1") (pin "A8") (pinfunction "SBU1_A8") (pintype "passive"))
    )
    (net (code "116") (name "unconnected-(USB1-SBU2-PadB8)") (class "Default")
      (node (ref "USB1") (pin "B8") (pinfunction "SBU2_B8") (pintype "passive"))
    )
    (net (code "117") (name "unconnected-(USB1-TX1+-PadA2)") (class "Default")
      (node (ref "USB1") (pin "A2") (pinfunction "TX1+_A2") (pintype "output"))
    )
    (net (code "118") (name "unconnected-(USB1-TX1--PadA3)") (class "Default")
      (node (ref "USB1") (pin "A3") (pinfunction "TX1-_A3") (pintype "output"))
    )
    (net (code "119") (name "unconnected-(USB1-TX2+-PadB2)") (class "Default")
      (node (ref "USB1") (pin "B2") (pinfunction "TX2+_B2") (pintype "output"))
    )
    (net (code "120") (name "unconnected-(USB1-TX2--PadB3)") (class "Default")
      (node (ref "USB1") (pin "B3") (pinfunction "TX2-_B3") (pintype "output"))
    )
  )
)
